# 3V3_LDO_Regulator.net
KiCad netlist of a schematic drawn in Altium Designer
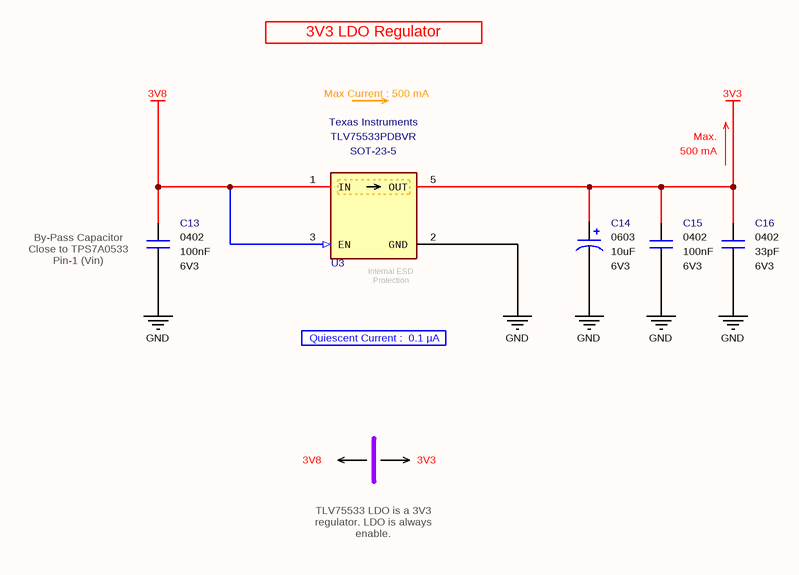
[diagram p0: 3V3 LDO Regulator.SchDoc]

(export (version "E")
  (design (tool "Eeschema 10.0.6"))
  (components
    (comp (ref "C13")
      (value "100nF")
      (footprint "CAPACITOR_0402")
      (description "Capacitor - 100nF [0402-6V3] (Ceramic)")
      (fields
        (field (name "CASE") "0402")
        (field (name "TOLERANCE") "%10")
        (field (name "VOLTAGE") "6V3")
        (field (name "MANUFACTURER PART NUMBER") "04026D104KAT4A")
      )
      (libsource (lib "Ovoo_Library") (part "Capacitor - 100nF [0402-6V3]"))
    )
    (comp (ref "C14")
      (value "10uF")
      (footprint "CAPACITOR_0603 - TANTALUM")
      (description "Capacitor - 10uF [0603] (Tantalium)")
      (fields
        (field (name "TOLERANCE") "20%")
        (field (name "CASE") "0603")
        (field (name "VOLTAGE") "6V3")
        (field (name "MANUFACTURER PART NUMBER") "F380J106MMAAH3")
      )
      (libsource (lib "Ovoo_Library") (part "Capacitor - 10uF [0603-6V3] (Tantalium)"))
    )
    (comp (ref "C15")
      (value "100nF")
      (footprint "CAPACITOR_0402")
      (description "Capacitor - 100nF [0402-6V3] (Ceramic)")
      (fields
        (field (name "TOLERANCE") "%10")
        (field (name "CASE") "0402")
        (field (name "VOLTAGE") "6V3")
        (field (name "MANUFACTURER PART NUMBER") "04026D104KAT4A")
      )
      (libsource (lib "Ovoo_Library") (part "Capacitor - 100nF [0402-6V3]"))
    )
    (comp (ref "C16")
      (value "33pF")
      (footprint "CAPACITOR_0402")
      (description "Capacitor - 33pF [0402] (Ceramic)")
      (fields
        (field (name "TOLERANCE") "10%")
        (field (name "CASE") "0402")
        (field (name "VOLTAGE") "6V3")
        (field (name "MANUFACTURER PART NUMBER") "C0402C330J9RACAUTO")
      )
      (libsource (lib "Ovoo_Library") (part "Capacitor - 33pF [0402-6V3]"))
    )
    (comp (ref "U3")
      (value "LDO Voltage Regulator")
      (footprint "SOT-23-5")
      (description "LDO Voltage Regulators 500-mA low-IQ small-size low-dropout (LDO) regulator.")
      (fields
        (field (name "CASE") "SOT-23-5")
        (field (name "MOUSER PART NUMBER") "595-TLV75533PDBVR")
        (field (name "MANUFACTURER PART NUMBER") "TLV75533PDBVR")
        (field (name "MANUFACTURER NAME") "Texas Instruments")
      )
      (libsource (lib "Ovoo_Library") (part "IC - TLV75533PDBVR"))
    )
  )
  (nets
    (net (code "1") (name "3V3") (class "Default")
      (node (ref "C14") (pin "1") (pinfunction "1_1") (pintype "passive"))
      (node (ref "C15") (pin "2") (pinfunction "2_2") (pintype "passive"))
      (node (ref "C16") (pin "1") (pinfunction "1_1") (pintype "passive"))
      (node (ref "U3") (pin "5") (pinfunction "OUT_5") (pintype "power_in"))
    )
    (net (code "2") (name "3V8") (class "Default")
      (node (ref "C13") (pin "1") (pinfunction "1_1") (pintype "passive"))
      (node (ref "U3") (pin "1") (pinfunction "IN_1") (pintype "power_in"))
      (node (ref "U3") (pin "3") (pinfunction "EN_3") (pintype "input"))
    )
    (net (code "3") (name "GND") (class "Default")
      (node (ref "C13") (pin "2") (pinfunction "2_2") (pintype "passive"))
      (node (ref "C14") (pin "2") (pinfunction "2_2") (pintype "passive"))
      (node (ref "C15") (pin "1") (pinfunction "1_1") (pintype "passive"))
      (node (ref "C16") (pin "2") (pinfunction "2_2") (pintype "passive"))
      (node (ref "U3") (pin "2") (pinfunction "GND_2") (pintype "passive"))
    )
    (net (code "4") (name "unconnected-(U3-NC-Pad4)") (class "Default")
      (node (ref "U3") (pin "4") (pinfunction "NC_4") (pintype "passive"))
    )
  )
)
